# HV_OPTO_METER.net
KiCad netlist of a schematic drawn in EasyEDA
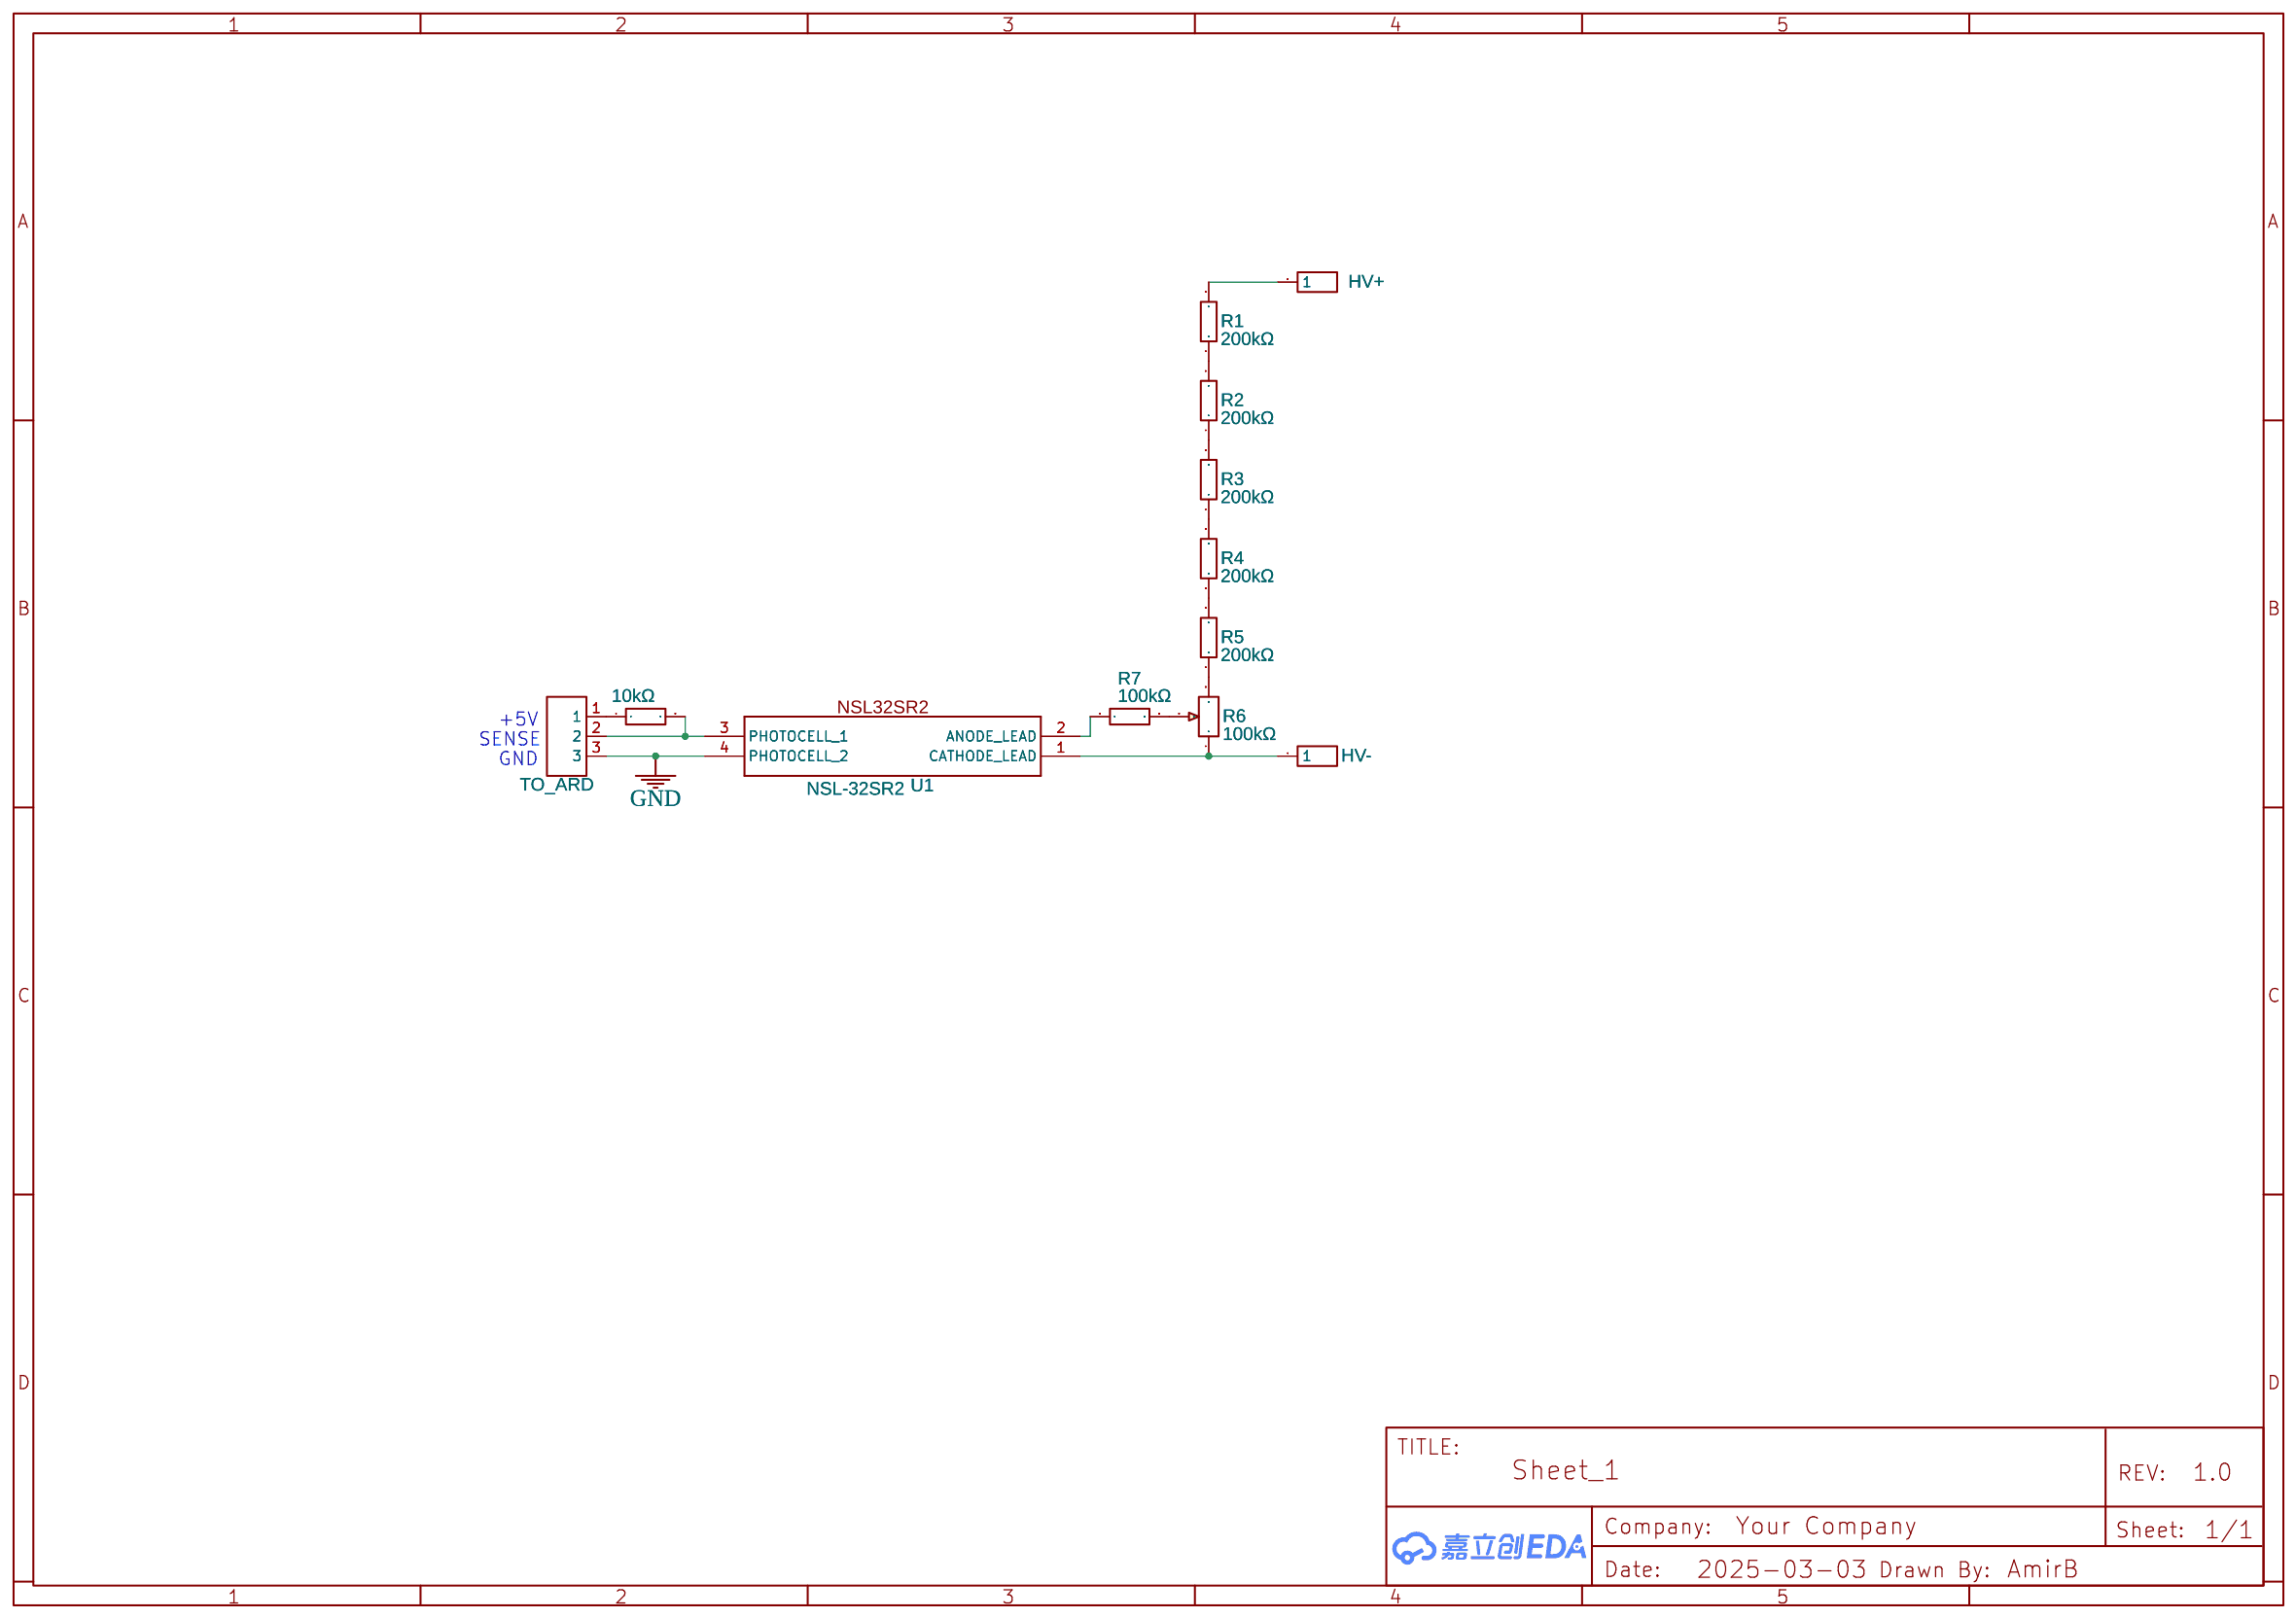
[diagram p0: schematic sheet]

(export (version "E")
  (design (tool "Eeschema 10.0.6"))
  (components
    (comp (ref "J1")
      (value "HV+")
      (fields (field (name "BOM_Supplier Part") "C81276"))
      (libsource (lib "") (part "HDR-M-2.54_1x1"))
    )
    (comp (ref "J2")
      (value "HV-")
      (fields (field (name "BOM_Supplier Part") "C81276"))
      (libsource (lib "") (part "HDR-M-2.54_1x1"))
    )
    (comp (ref "R1")
      (value "200kΩ")
      (fields
        (field (name "Manufacturer Part") "RN1/2W200KΩFT/BA1")
        (field (name "Manufacturer") "Tyohm(幸亚电阻)")
      )
      (libsource (lib "") (part "RN1/2W200KΩFT/BA1"))
    )
    (comp (ref "R2")
      (value "200kΩ")
      (fields
        (field (name "Manufacturer Part") "RN1/2W200KΩFT/BA1")
        (field (name "Manufacturer") "Tyohm(幸亚电阻)")
      )
      (libsource (lib "") (part "RN1/2W200KΩFT/BA1"))
    )
    (comp (ref "R3")
      (value "200kΩ")
      (fields
        (field (name "Manufacturer Part") "RN1/2W200KΩFT/BA1")
        (field (name "Manufacturer") "Tyohm(幸亚电阻)")
      )
      (libsource (lib "") (part "RN1/2W200KΩFT/BA1"))
    )
    (comp (ref "R4")
      (value "200kΩ")
      (fields
        (field (name "Manufacturer Part") "RN1/2W200KΩFT/BA1")
        (field (name "Manufacturer") "Tyohm(幸亚电阻)")
      )
      (libsource (lib "") (part "RN1/2W200KΩFT/BA1"))
    )
    (comp (ref "R5")
      (value "200kΩ")
      (fields
        (field (name "Manufacturer Part") "RN1/2W200KΩFT/BA1")
        (field (name "Manufacturer") "Tyohm(幸亚电阻)")
      )
      (libsource (lib "") (part "RN1/2W200KΩFT/BA1"))
    )
    (comp (ref "R6")
      (value "100kΩ")
      (fields (field (name "Manufacturer Part") "3296W-1-104") (field (name "Manufacturer") "BOCHEN(博晨)"))
      (libsource (lib "") (part "3296W-1-104"))
    )
    (comp (ref "R7")
      (value "100kΩ")
      (fields
        (field (name "Manufacturer Part") "0805W8F1003T5E")
        (field (name "Manufacturer") "UNI-ROYAL(厚声)")
      )
      (libsource (lib "") (part "0805W8F1003T5E_C149504"))
    )
    (comp (ref "RPUP")
      (value "10kΩ")
      (fields
        (field (name "BOM_Manufacturer Part") "0603WAF1002T5E")
        (field (name "BOM_Supplier Part") "C25804")
      )
      (libsource (lib "") (part "0603WAF1002T5E"))
    )
    (comp (ref "TO_ARD")
      (value "FK2510")
      (fields (field (name "Manufacturer Part") "2510-3A") (field (name "Manufacturer") "BOOMELE(博穆精密)"))
      (libsource (lib "") (part "kf2510_3A"))
    )
    (comp (ref "U1") (value "NSL-32SR2") (libsource (lib "") (part "NSL-32SR2")))
  )
  (nets
    (net (code "1") (name "GND") (class "Default")
      (node (ref "TO_ARD") (pin "3") (pinfunction "3_3") (pintype "unspecified"))
      (node (ref "U1") (pin "4") (pinfunction "PHOTOCELL_2_4") (pintype "bidirectional"))
    )
    (net (code "2") (name "Net-(J1-Pad1)") (class "Default")
      (node (ref "J1") (pin "1") (pinfunction "1_1") (pintype "input"))
      (node (ref "R1") (pin "2") (pinfunction "2_2") (pintype "unspecified"))
    )
    (net (code "3") (name "Net-(R1-Pad1)") (class "Default")
      (node (ref "R1") (pin "1") (pinfunction "1_1") (pintype "unspecified"))
      (node (ref "R2") (pin "2") (pinfunction "2_2") (pintype "unspecified"))
    )
    (net (code "4") (name "Net-(R2-Pad1)") (class "Default")
      (node (ref "R2") (pin "1") (pinfunction "1_1") (pintype "unspecified"))
      (node (ref "R3") (pin "2") (pinfunction "2_2") (pintype "unspecified"))
    )
    (net (code "5") (name "Net-(R3-Pad1)") (class "Default")
      (node (ref "R3") (pin "1") (pinfunction "1_1") (pintype "unspecified"))
      (node (ref "R4") (pin "2") (pinfunction "2_2") (pintype "unspecified"))
    )
    (net (code "6") (name "Net-(R4-Pad1)") (class "Default")
      (node (ref "R4") (pin "1") (pinfunction "1_1") (pintype "unspecified"))
      (node (ref "R5") (pin "2") (pinfunction "2_2") (pintype "unspecified"))
    )
    (net (code "7") (name "Net-(R5-Pad1)") (class "Default")
      (node (ref "R5") (pin "1") (pinfunction "1_1") (pintype "unspecified"))
      (node (ref "R6") (pin "3") (pinfunction "3_3") (pintype "input"))
    )
    (net (code "8") (name "Net-(R6-Pad2)") (class "Default")
      (node (ref "R6") (pin "2") (pinfunction "2_2") (pintype "input"))
      (node (ref "R7") (pin "2") (pinfunction "2_2") (pintype "unspecified"))
    )
    (net (code "9") (name "Net-(RPUP-Pad1)") (class "Default")
      (node (ref "RPUP") (pin "1") (pinfunction "1_1") (pintype "input"))
      (node (ref "TO_ARD") (pin "1") (pinfunction "1_1") (pintype "unspecified"))
    )
    (net (code "10") (name "Net-(U1-ANODE_LEAD)") (class "Default")
      (node (ref "R7") (pin "1") (pinfunction "1_1") (pintype "unspecified"))
      (node (ref "U1") (pin "2") (pinfunction "ANODE_LEAD_2") (pintype "bidirectional"))
    )
    (net (code "11") (name "Net-(U1-CATHODE_LEAD)") (class "Default")
      (node (ref "J2") (pin "1") (pinfunction "1_1") (pintype "input"))
      (node (ref "R6") (pin "1") (pinfunction "1_1") (pintype "input"))
      (node (ref "U1") (pin "1") (pinfunction "CATHODE_LEAD_1") (pintype "bidirectional"))
    )
    (net (code "12") (name "Net-(U1-PHOTOCELL_1)") (class "Default")
      (node (ref "RPUP") (pin "2") (pinfunction "2_2") (pintype "input"))
      (node (ref "TO_ARD") (pin "2") (pinfunction "2_2") (pintype "unspecified"))
      (node (ref "U1") (pin "3") (pinfunction "PHOTOCELL_1_3") (pintype "bidirectional"))
    )
  )
)
